# SENSORS.net
KiCad netlist of a schematic drawn in Altium Designer
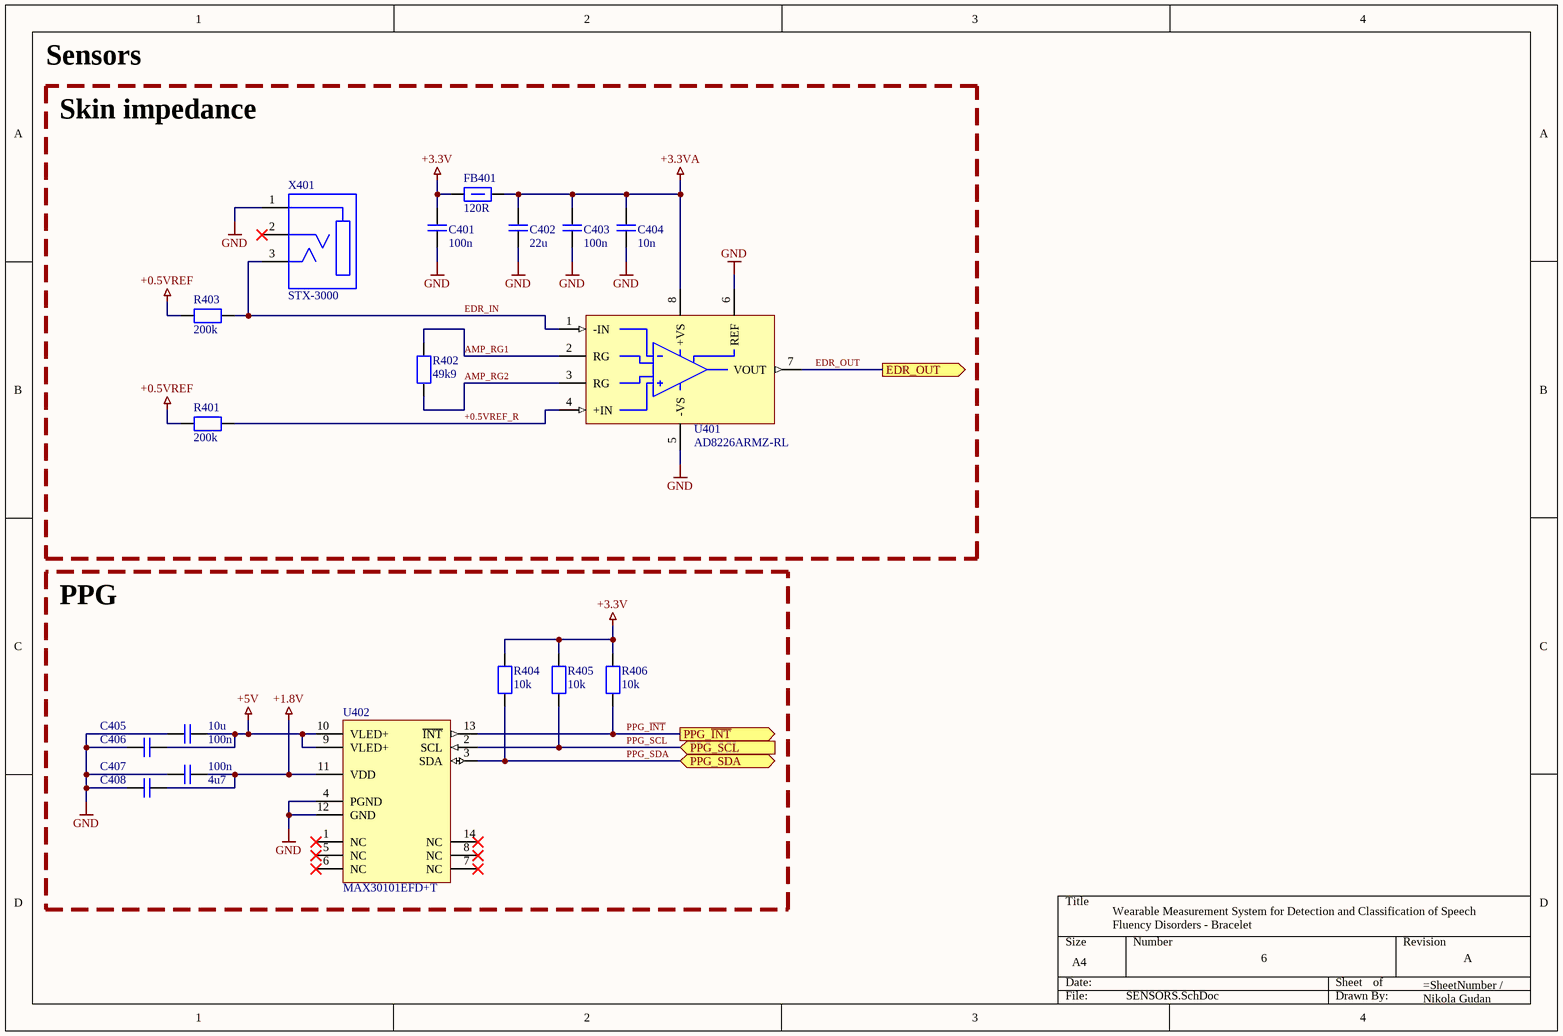
[diagram p0: SENSORS.SchDoc]

(export (version "E")
  (design (tool "Eeschema 10.0.6"))
  (components
    (comp (ref "C401")
      (value "100n")
      (footprint "CAPC0603")
      (description "Ceramic capacitor, 100nF,  50V, X7R")
      (fields (field (name "MFR") "KEMET") (field (name "CHECKED") "Yes"))
      (libsource (lib "NG_Passive") (part "CAPC0603-100n-10"))
    )
    (comp (ref "C402")
      (value "22u")
      (footprint "CAPC0603")
      (description "Ceramic capacitor, 22uF,  10V, X5R")
      (fields (field (name "MFR") "Samsung Electro-Mechanics") (field (name "CHECKED") "Yes"))
      (libsource (lib "NG_Passive") (part "CAPC0603-22u-20"))
    )
    (comp (ref "C403")
      (value "100n")
      (footprint "CAPC0603")
      (description "Ceramic capacitor, 100nF,  50V, X7R")
      (fields (field (name "MFR") "KEMET") (field (name "CHECKED") "Yes"))
      (libsource (lib "NG_Passive") (part "CAPC0603-100n-10"))
    )
    (comp (ref "C404")
      (value "10n")
      (footprint "CAPC0603")
      (description "Ceramic capacitor, 10nF,  50V, X7R")
      (fields (field (name "MFR") "KEMET") (field (name "CHECKED") "Yes"))
      (libsource (lib "NG_Passive") (part "CAPC0603-10n-20"))
    )
    (comp (ref "C405")
      (value "10u")
      (footprint "CAPC0603")
      (description "Ceramic capacitor, 10uF,  25V, X5R")
      (fields (field (name "MFR") "TAIYO YUDEN") (field (name "CHECKED") "Yes"))
      (libsource (lib "NG_Passive") (part "CAPC0603-10u-20"))
    )
    (comp (ref "C406")
      (value "100n")
      (footprint "CAPC0603")
      (description "Ceramic capacitor, 100nF,  50V, X7R")
      (fields (field (name "MFR") "KEMET") (field (name "CHECKED") "Yes"))
      (libsource (lib "NG_Passive") (part "CAPC0603-100n-10"))
    )
    (comp (ref "C407")
      (value "100n")
      (footprint "CAPC0603")
      (description "Ceramic capacitor, 100nF,  50V, X7R")
      (fields (field (name "MFR") "KEMET") (field (name "CHECKED") "Yes"))
      (libsource (lib "NG_Passive") (part "CAPC0603-100n-10"))
    )
    (comp (ref "C408")
      (value "4u7")
      (footprint "CAPC0603")
      (description "Ceramic capacitor, 4.7uF, 25V, X5R")
      (fields (field (name "MFR") "TDK") (field (name "CHECKED") "Yes"))
      (libsource (lib "NG_Passive") (part "CAPC0603-4u7-10"))
    )
    (comp (ref "FB401")
      (value "120R")
      (footprint "FBC0603")
      (description "Ferrite bead, 120R@100MHz")
      (fields (field (name "MFR") "TDK Corporation") (field (name "CHECKED") "Yes"))
      (libsource (lib "NG_Passive") (part "FB0603-120R"))
    )
    (comp (ref "R401")
      (value "200k")
      (footprint "RESC0603")
      (description "Thick film resistor, 200kOhms, 100mW")
      (fields (field (name "MFR") "YAGEO") (field (name "CHECKED") "Yes"))
      (libsource (lib "NG_Passive") (part "RES0603-200k-1"))
    )
    (comp (ref "R402")
      (value "49k9")
      (footprint "RESC0603")
      (description "Thick film resistor, 49.9kOhms, 100mW")
      (fields (field (name "MFR") "YAGEO") (field (name "CHECKED") "Yes"))
      (libsource (lib "NG_Passive") (part "RES0603-49k9-1"))
    )
    (comp (ref "R403")
      (value "200k")
      (footprint "RESC0805")
      (description "Thick film resistor, 200k, 125mW")
      (fields (field (name "MFR") "YAGEO") (field (name "CHECKED") "No"))
      (libsource (lib "NG_Passive") (part "RES0805-200k-1"))
    )
    (comp (ref "R404")
      (value "10k")
      (footprint "RESC0603")
      (description "Thick film resistor, 10kOhm, 100mW")
      (fields (field (name "MFR") "YAGEO") (field (name "CHECKED") "Yes"))
      (libsource (lib "NG_Passive") (part "RES0603-10k-1"))
    )
    (comp (ref "R405")
      (value "10k")
      (footprint "RESC0603")
      (description "Thick film resistor, 10kOhm, 100mW")
      (fields (field (name "MFR") "YAGEO") (field (name "CHECKED") "Yes"))
      (libsource (lib "NG_Passive") (part "RES0603-10k-1"))
    )
    (comp (ref "R406")
      (value "10k")
      (footprint "RESC0603")
      (description "Thick film resistor, 10kOhm, 100mW")
      (fields (field (name "MFR") "YAGEO") (field (name "CHECKED") "Yes"))
      (libsource (lib "NG_Passive") (part "RES0603-10k-1"))
    )
    (comp (ref "U401")
      (value "AD8226ARMZ-RL")
      (footprint "SOP65P530X110-8")
      (description "Instrumentation Amplifier, 1 CH")
      (fields (field (name "MFR") "Analog Devices") (field (name "CHECKED") "No"))
      (libsource (lib "NG_Analog") (part "AD8226ARMZ-RL"))
    )
    (comp (ref "U402")
      (value "MAX30101EFD+T")
      (footprint "QFN80P330X560X155-14")
      (description "Pulse Oximeter and Heart-Rate Sensor for Wearable Health")
      (fields (field (name "MFR") "Analog Devices Inc./Maxim Integrated") (field (name "CHECKED") "No"))
      (libsource (lib "NG_Analog") (part "BIO IC MAX30101EFD+T"))
    )
    (comp (ref "X401")
      (value "STX-3000")
      (footprint "AUDIO STX-3000")
      (description "3.5mm Audio connector, 3POS")
      (fields (field (name "MFR") "Kycon") (field (name "CHECKED") "No"))
      (libsource (lib "NG_Mechanical") (part "AUDIO STX-3000"))
    )
  )
  (nets
    (net (code "1") (name "+0.5VREF") (class "Default")
      (node (ref "R401") (pin "2") (pinfunction "2_2") (pintype "passive"))
      (node (ref "R403") (pin "1") (pinfunction "1_1") (pintype "passive"))
    )
    (net (code "2") (name "+1.8V") (class "Default")
      (node (ref "C407") (pin "2") (pinfunction "2_2") (pintype "passive"))
      (node (ref "C408") (pin "2") (pinfunction "2_2") (pintype "passive"))
      (node (ref "U402") (pin "11") (pinfunction "VDD_11") (pintype "power_in"))
    )
    (net (code "3") (name "+3.3V") (class "Default")
      (node (ref "C401") (pin "2") (pinfunction "2_2") (pintype "passive"))
      (node (ref "FB401") (pin "1") (pinfunction "1_1") (pintype "passive"))
      (node (ref "R404") (pin "2") (pinfunction "2_2") (pintype "passive"))
      (node (ref "R405") (pin "2") (pinfunction "2_2") (pintype "passive"))
      (node (ref "R406") (pin "2") (pinfunction "2_2") (pintype "passive"))
    )
    (net (code "4") (name "+3.3VA") (class "Default")
      (node (ref "C402") (pin "2") (pinfunction "2_2") (pintype "passive"))
      (node (ref "C403") (pin "2") (pinfunction "2_2") (pintype "passive"))
      (node (ref "C404") (pin "2") (pinfunction "2_2") (pintype "passive"))
      (node (ref "FB401") (pin "2") (pinfunction "2_2") (pintype "passive"))
      (node (ref "U401") (pin "8") (pinfunction "+VS_8") (pintype "power_in"))
    )
    (net (code "5") (name "+5V") (class "Default")
      (node (ref "C405") (pin "2") (pinfunction "2_2") (pintype "passive"))
      (node (ref "C406") (pin "2") (pinfunction "2_2") (pintype "passive"))
      (node (ref "U402") (pin "10") (pinfunction "VLED+_10") (pintype "power_in"))
      (node (ref "U402") (pin "9") (pinfunction "VLED+_9") (pintype "power_in"))
    )
    (net (code "6") (name "/+0.5VREF_R") (class "Default")
      (node (ref "R401") (pin "1") (pinfunction "1_1") (pintype "passive"))
      (node (ref "U401") (pin "4") (pinfunction "+IN_4") (pintype "input"))
    )
    (net (code "7") (name "/AMP_RG1") (class "Default")
      (node (ref "R402") (pin "2") (pinfunction "2_2") (pintype "passive"))
      (node (ref "U401") (pin "2") (pinfunction "RG_2") (pintype "passive"))
    )
    (net (code "8") (name "/AMP_RG2") (class "Default")
      (node (ref "R402") (pin "1") (pinfunction "1_1") (pintype "passive"))
      (node (ref "U401") (pin "3") (pinfunction "RG_3") (pintype "passive"))
    )
    (net (code "9") (name "/EDR_IN") (class "Default")
      (node (ref "R403") (pin "2") (pinfunction "2_2") (pintype "passive"))
      (node (ref "U401") (pin "1") (pinfunction "-IN_1") (pintype "input"))
      (node (ref "X401") (pin "3") (pinfunction "3_3") (pintype "passive"))
    )
    (net (code "10") (name "/EDR_OUT") (class "Default")
      (node (ref "U401") (pin "7") (pinfunction "VOUT_7") (pintype "output"))
    )
    (net (code "11") (name "/PPG_SCL") (class "Default")
      (node (ref "R405") (pin "1") (pinfunction "1_1") (pintype "passive"))
      (node (ref "U402") (pin "2") (pinfunction "SCL_2") (pintype "input"))
    )
    (net (code "12") (name "/PPG_SDA") (class "Default")
      (node (ref "R404") (pin "1") (pinfunction "1_1") (pintype "passive"))
      (node (ref "U402") (pin "3") (pinfunction "SDA_3") (pintype "bidirectional"))
    )
    (net (code "13") (name "/PPG_~{INT}") (class "Default")
      (node (ref "R406") (pin "1") (pinfunction "1_1") (pintype "passive"))
      (node (ref "U402") (pin "13") (pinfunction "~{INT}_13") (pintype "output"))
    )
    (net (code "14") (name "GND") (class "Default")
      (node (ref "C401") (pin "1") (pinfunction "1_1") (pintype "passive"))
      (node (ref "C402") (pin "1") (pinfunction "1_1") (pintype "passive"))
      (node (ref "C403") (pin "1") (pinfunction "1_1") (pintype "passive"))
      (node (ref "C404") (pin "1") (pinfunction "1_1") (pintype "passive"))
      (node (ref "C405") (pin "1") (pinfunction "1_1") (pintype "passive"))
      (node (ref "C406") (pin "1") (pinfunction "1_1") (pintype "passive"))
      (node (ref "C407") (pin "1") (pinfunction "1_1") (pintype "passive"))
      (node (ref "C408") (pin "1") (pinfunction "1_1") (pintype "passive"))
      (node (ref "U401") (pin "5") (pinfunction "-VS_5") (pintype "power_in"))
      (node (ref "U401") (pin "6") (pinfunction "REF_6") (pintype "power_in"))
      (node (ref "U402") (pin "12") (pinfunction "GND_12") (pintype "power_in"))
      (node (ref "U402") (pin "4") (pinfunction "PGND_4") (pintype "power_in"))
      (node (ref "X401") (pin "1") (pinfunction "1_1") (pintype "passive"))
    )
    (net (code "15") (name "unconnected-(U402-NC-Pad1)") (class "Default")
      (node (ref "U402") (pin "1") (pinfunction "NC_1") (pintype "passive+no_connect"))
    )
    (net (code "16") (name "unconnected-(U402-NC-Pad5)") (class "Default")
      (node (ref "U402") (pin "5") (pinfunction "NC_5") (pintype "passive+no_connect"))
    )
    (net (code "17") (name "unconnected-(U402-NC-Pad6)") (class "Default")
      (node (ref "U402") (pin "6") (pinfunction "NC_6") (pintype "passive+no_connect"))
    )
    (net (code "18") (name "unconnected-(U402-NC-Pad7)") (class "Default")
      (node (ref "U402") (pin "7") (pinfunction "NC_7") (pintype "passive+no_connect"))
    )
    (net (code "19") (name "unconnected-(U402-NC-Pad8)") (class "Default")
      (node (ref "U402") (pin "8") (pinfunction "NC_8") (pintype "passive+no_connect"))
    )
    (net (code "20") (name "unconnected-(U402-NC-Pad14)") (class "Default")
      (node (ref "U402") (pin "14") (pinfunction "NC_14") (pintype "passive+no_connect"))
    )
    (net (code "21") (name "unconnected-(X401-Pad2)") (class "Default")
      (node (ref "X401") (pin "2") (pinfunction "2_2") (pintype "passive+no_connect"))
    )
  )
)
